# Memory.net
KiCad netlist of a schematic drawn in Altium Designer
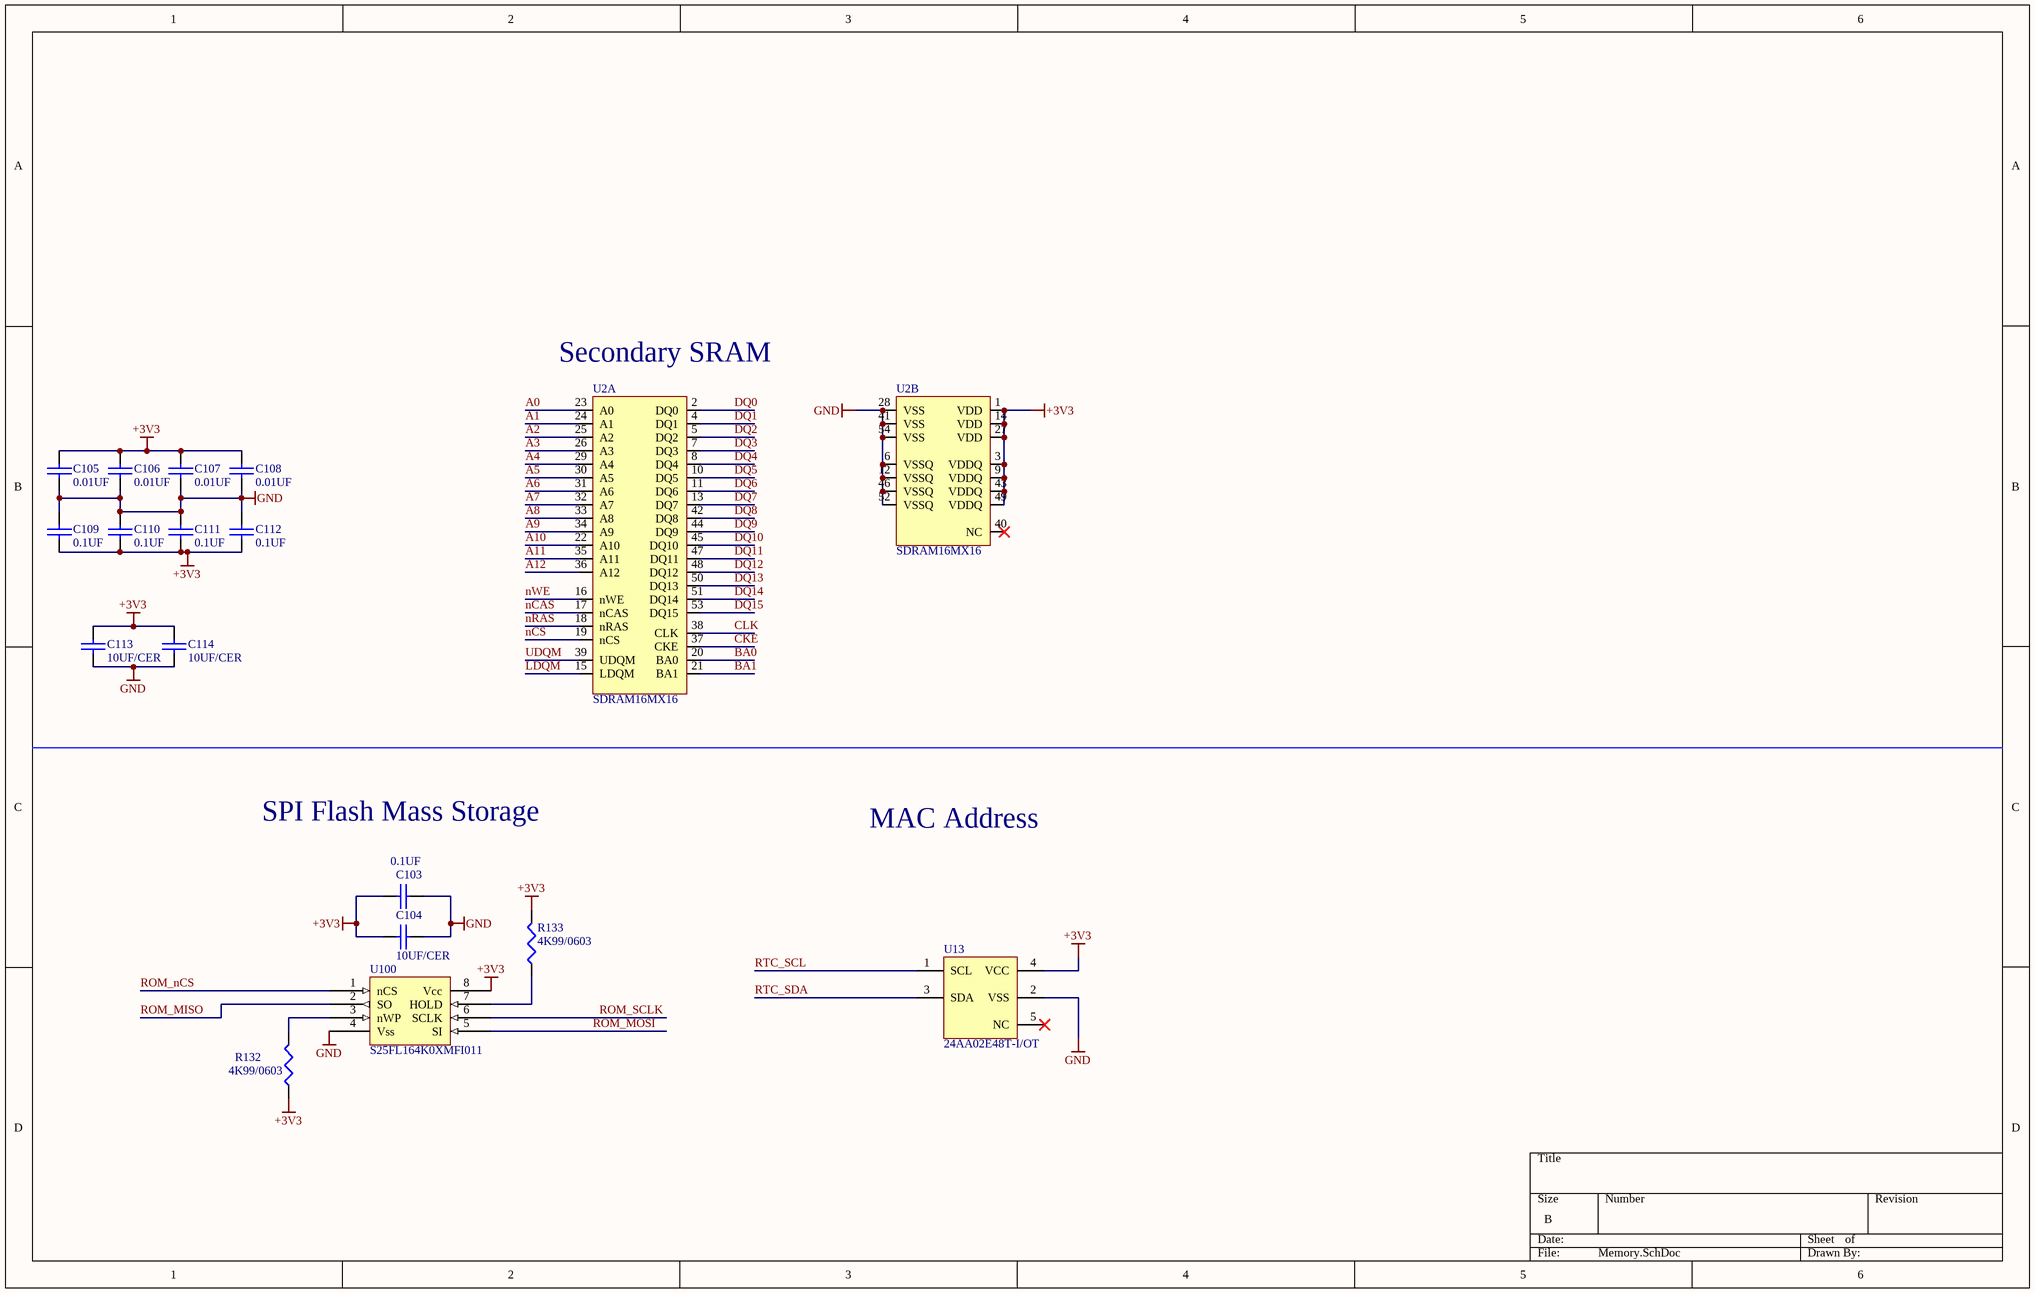
[diagram p0: Memory.SchDoc]

(export (version "E")
  (design (tool "Eeschema 10.0.6"))
  (components
    (comp (ref "C103")
      (value "0.1UF")
      (footprint "0603")
      (description "CAP .10UF 16V CERAMIC X7R 0603")
      (fields (field (name "MFG") "Kemet"))
      (libsource (lib "C64Interface") (part "0.1UF"))
    )
    (comp (ref "C104")
      (value "10UF/CER")
      (footprint "0805")
      (description "10µF ±10% 25V Ceramic Capacitor X7S 0805")
      (libsource (lib "*") (part "10UF/CER"))
    )
    (comp (ref "C105")
      (value "0.01UF")
      (footprint "0603")
      (description "10000pF ±10% 10V Ceramic Capacitor X7R 0603 (1608 Metric)")
      (fields (field (name "MFG") "Kemet"))
      (libsource (lib "C64Interface") (part "0.01UF"))
    )
    (comp (ref "C106")
      (value "0.01UF")
      (footprint "0603")
      (description "10000pF ±10% 10V Ceramic Capacitor X7R 0603 (1608 Metric)")
      (fields (field (name "MFG") "Kemet"))
      (libsource (lib "C64Interface") (part "0.01UF"))
    )
    (comp (ref "C107")
      (value "0.01UF")
      (footprint "0603")
      (description "10000pF ±10% 10V Ceramic Capacitor X7R 0603 (1608 Metric)")
      (fields (field (name "MFG") "Kemet"))
      (libsource (lib "C64Interface") (part "0.01UF"))
    )
    (comp (ref "C108")
      (value "0.01UF")
      (footprint "0603")
      (description "10000pF ±10% 10V Ceramic Capacitor X7R 0603 (1608 Metric)")
      (fields (field (name "MFG") "Kemet"))
      (libsource (lib "C64Interface") (part "0.01UF"))
    )
    (comp (ref "C109")
      (value "0.1UF")
      (footprint "0603")
      (description "CAP .10UF 16V CERAMIC X7R 0603")
      (fields (field (name "MFG") "Kemet"))
      (libsource (lib "C64Interface") (part "0.1UF"))
    )
    (comp (ref "C110")
      (value "0.1UF")
      (footprint "0603")
      (description "CAP .10UF 16V CERAMIC X7R 0603")
      (fields (field (name "MFG") "Kemet"))
      (libsource (lib "C64Interface") (part "0.1UF"))
    )
    (comp (ref "C111")
      (value "0.1UF")
      (footprint "0603")
      (description "CAP .10UF 16V CERAMIC X7R 0603")
      (fields (field (name "MFG") "Kemet"))
      (libsource (lib "C64Interface") (part "0.1UF"))
    )
    (comp (ref "C112")
      (value "0.1UF")
      (footprint "0603")
      (description "CAP .10UF 16V CERAMIC X7R 0603")
      (fields (field (name "MFG") "Kemet"))
      (libsource (lib "C64Interface") (part "0.1UF"))
    )
    (comp (ref "C113")
      (value "10UF/CER")
      (footprint "0805")
      (description "10µF ±10% 25V Ceramic Capacitor X7S 0805")
      (libsource (lib "C64Interface") (part "10UF/CER"))
    )
    (comp (ref "C114")
      (value "10UF/CER")
      (footprint "0805")
      (description "10µF ±10% 25V Ceramic Capacitor X7S 0805")
      (libsource (lib "C64Interface") (part "10UF/CER"))
    )
    (comp (ref "R132")
      (value "4K99/0603")
      (footprint "0603")
      (description "RES 4.99K OHM 1/10W 1% 0603 SMD")
      (fields (field (name "MFG") "Dale/Vishay"))
      (libsource (lib "C64Interface") (part "4K99/0603"))
    )
    (comp (ref "R133")
      (value "4K99/0603")
      (footprint "0603")
      (description "RES 4.99K OHM 1/10W 1% 0603 SMD")
      (fields (field (name "MFG") "Dale/Vishay"))
      (libsource (lib "C64Interface") (part "4K99/0603"))
    )
    (comp (ref "U2")
      (value "SDRAM16MX16")
      (footprint "SOP54")
      (description "SDRAM Memory IC 256Mb (16M x 16) Parallel 166MHz 5ns 54-TSOP II")
      (fields (field (name "MFG") "Winbond"))
      (libsource (lib "C64Interface") (part "SDRAM16MX16"))
    )
    (comp (ref "U13")
      (value "24AA02E48T-I/OT")
      (footprint "SOT23-5")
      (description "IC EEPROM 2KBIT 400KHZ SOT23-5")
      (fields (field (name "MFG") "Microchip"))
      (libsource (lib "APN") (part "24AA02E48T-I/OT"))
    )
    (comp (ref "U100")
      (value "S25FL164K0XMFI011")
      (footprint "SOC008")
      (description "IC FLASH 64MBIT 108MHZ 8SOIC")
      (libsource (lib "C64Interface") (part "S25FL164K0XMFI011"))
    )
  )
  (nets
    (net (code "1") (name "+3V3") (class "Default")
      (node (ref "C103") (pin "1") (pintype "passive"))
      (node (ref "C104") (pin "1") (pintype "passive"))
      (node (ref "C105") (pin "1") (pintype "passive"))
      (node (ref "C106") (pin "1") (pintype "passive"))
      (node (ref "C107") (pin "1") (pintype "passive"))
      (node (ref "C108") (pin "1") (pintype "passive"))
      (node (ref "C109") (pin "2") (pintype "passive"))
      (node (ref "C110") (pin "2") (pintype "passive"))
      (node (ref "C111") (pin "2") (pintype "passive"))
      (node (ref "C112") (pin "2") (pintype "passive"))
      (node (ref "C113") (pin "2") (pintype "passive"))
      (node (ref "C114") (pin "2") (pintype "passive"))
      (node (ref "R132") (pin "1") (pintype "passive"))
      (node (ref "R133") (pin "2") (pintype "passive"))
      (node (ref "U100") (pin "8") (pinfunction "Vcc_8") (pintype "power_in"))
      (node (ref "U13") (pin "4") (pinfunction "VCC_4") (pintype "power_in"))
      (node (ref "U2") (pin "1") (pinfunction "VDD_1") (pintype "passive"))
      (node (ref "U2") (pin "14") (pinfunction "VDD_14") (pintype "passive"))
      (node (ref "U2") (pin "27") (pinfunction "VDD_27") (pintype "passive"))
      (node (ref "U2") (pin "3") (pinfunction "VDDQ_3") (pintype "passive"))
      (node (ref "U2") (pin "43") (pinfunction "VDDQ_43") (pintype "passive"))
      (node (ref "U2") (pin "49") (pinfunction "VDDQ_49") (pintype "passive"))
      (node (ref "U2") (pin "9") (pinfunction "VDDQ_9") (pintype "passive"))
    )
    (net (code "2") (name "/A0") (class "Default")
      (node (ref "U2") (pin "23") (pinfunction "A0_23") (pintype "passive"))
    )
    (net (code "3") (name "/A1") (class "Default")
      (node (ref "U2") (pin "24") (pinfunction "A1_24") (pintype "passive"))
    )
    (net (code "4") (name "/A2") (class "Default")
      (node (ref "U2") (pin "25") (pinfunction "A2_25") (pintype "passive"))
    )
    (net (code "5") (name "/A3") (class "Default")
      (node (ref "U2") (pin "26") (pinfunction "A3_26") (pintype "passive"))
    )
    (net (code "6") (name "/A4") (class "Default")
      (node (ref "U2") (pin "29") (pinfunction "A4_29") (pintype "passive"))
    )
    (net (code "7") (name "/A5") (class "Default")
      (node (ref "U2") (pin "30") (pinfunction "A5_30") (pintype "passive"))
    )
    (net (code "8") (name "/A6") (class "Default")
      (node (ref "U2") (pin "31") (pinfunction "A6_31") (pintype "passive"))
    )
    (net (code "9") (name "/A7") (class "Default")
      (node (ref "U2") (pin "32") (pinfunction "A7_32") (pintype "passive"))
    )
    (net (code "10") (name "/A8") (class "Default")
      (node (ref "U2") (pin "33") (pinfunction "A8_33") (pintype "passive"))
    )
    (net (code "11") (name "/A9") (class "Default")
      (node (ref "U2") (pin "34") (pinfunction "A9_34") (pintype "passive"))
    )
    (net (code "12") (name "/A10") (class "Default")
      (node (ref "U2") (pin "22") (pinfunction "A10_22") (pintype "passive"))
    )
    (net (code "13") (name "/A11") (class "Default")
      (node (ref "U2") (pin "35") (pinfunction "A11_35") (pintype "passive"))
    )
    (net (code "14") (name "/A12") (class "Default")
      (node (ref "U2") (pin "36") (pinfunction "A12_36") (pintype "passive"))
    )
    (net (code "15") (name "/BA0") (class "Default")
      (node (ref "U2") (pin "20") (pinfunction "BA0_20") (pintype "passive"))
    )
    (net (code "16") (name "/BA1") (class "Default")
      (node (ref "U2") (pin "21") (pinfunction "BA1_21") (pintype "passive"))
    )
    (net (code "17") (name "/CKE") (class "Default")
      (node (ref "U2") (pin "37") (pinfunction "CKE_37") (pintype "passive"))
    )
    (net (code "18") (name "/CLK") (class "Default")
      (node (ref "U2") (pin "38") (pinfunction "CLK_38") (pintype "passive"))
    )
    (net (code "19") (name "/DQ0") (class "Default")
      (node (ref "U2") (pin "2") (pinfunction "DQ0_2") (pintype "passive"))
    )
    (net (code "20") (name "/DQ1") (class "Default")
      (node (ref "U2") (pin "4") (pinfunction "DQ1_4") (pintype "passive"))
    )
    (net (code "21") (name "/DQ2") (class "Default")
      (node (ref "U2") (pin "5") (pinfunction "DQ2_5") (pintype "passive"))
    )
    (net (code "22") (name "/DQ3") (class "Default")
      (node (ref "U2") (pin "7") (pinfunction "DQ3_7") (pintype "passive"))
    )
    (net (code "23") (name "/DQ4") (class "Default")
      (node (ref "U2") (pin "8") (pinfunction "DQ4_8") (pintype "passive"))
    )
    (net (code "24") (name "/DQ5") (class "Default")
      (node (ref "U2") (pin "10") (pinfunction "DQ5_10") (pintype "passive"))
    )
    (net (code "25") (name "/DQ6") (class "Default")
      (node (ref "U2") (pin "11") (pinfunction "DQ6_11") (pintype "passive"))
    )
    (net (code "26") (name "/DQ7") (class "Default")
      (node (ref "U2") (pin "13") (pinfunction "DQ7_13") (pintype "passive"))
    )
    (net (code "27") (name "/DQ8") (class "Default")
      (node (ref "U2") (pin "42") (pinfunction "DQ8_42") (pintype "passive"))
    )
    (net (code "28") (name "/DQ9") (class "Default")
      (node (ref "U2") (pin "44") (pinfunction "DQ9_44") (pintype "passive"))
    )
    (net (code "29") (name "/DQ10") (class "Default")
      (node (ref "U2") (pin "45") (pinfunction "DQ10_45") (pintype "passive"))
    )
    (net (code "30") (name "/DQ11") (class "Default")
      (node (ref "U2") (pin "47") (pinfunction "DQ11_47") (pintype "passive"))
    )
    (net (code "31") (name "/DQ12") (class "Default")
      (node (ref "U2") (pin "48") (pinfunction "DQ12_48") (pintype "passive"))
    )
    (net (code "32") (name "/DQ13") (class "Default")
      (node (ref "U2") (pin "50") (pinfunction "DQ13_50") (pintype "passive"))
    )
    (net (code "33") (name "/DQ14") (class "Default")
      (node (ref "U2") (pin "51") (pinfunction "DQ14_51") (pintype "passive"))
    )
    (net (code "34") (name "/DQ15") (class "Default")
      (node (ref "U2") (pin "53") (pinfunction "DQ15_53") (pintype "passive"))
    )
    (net (code "35") (name "/LDQM") (class "Default")
      (node (ref "U2") (pin "15") (pinfunction "LDQM_15") (pintype "passive"))
    )
    (net (code "36") (name "/ROM_MISO") (class "Default")
      (node (ref "U100") (pin "2") (pinfunction "SO_2") (pintype "output"))
    )
    (net (code "37") (name "/ROM_MOSI") (class "Default")
      (node (ref "U100") (pin "5") (pinfunction "SI_5") (pintype "input"))
    )
    (net (code "38") (name "/ROM_SCLK") (class "Default")
      (node (ref "U100") (pin "6") (pinfunction "SCLK_6") (pintype "input"))
    )
    (net (code "39") (name "/ROM_nCS") (class "Default")
      (node (ref "U100") (pin "1") (pinfunction "nCS_1") (pintype "input"))
    )
    (net (code "40") (name "/RTC_SCL") (class "Default")
      (node (ref "U13") (pin "1") (pinfunction "SCL_1") (pintype "power_in"))
    )
    (net (code "41") (name "/RTC_SDA") (class "Default")
      (node (ref "U13") (pin "3") (pinfunction "SDA_3") (pintype "power_in"))
    )
    (net (code "42") (name "/UDQM") (class "Default")
      (node (ref "U2") (pin "39") (pinfunction "UDQM_39") (pintype "passive"))
    )
    (net (code "43") (name "/nCAS") (class "Default")
      (node (ref "U2") (pin "17") (pinfunction "nCAS_17") (pintype "passive"))
    )
    (net (code "44") (name "/nCS") (class "Default")
      (node (ref "U2") (pin "19") (pinfunction "nCS_19") (pintype "passive"))
    )
    (net (code "45") (name "/nRAS") (class "Default")
      (node (ref "U2") (pin "18") (pinfunction "nRAS_18") (pintype "passive"))
    )
    (net (code "46") (name "/nWE") (class "Default")
      (node (ref "U2") (pin "16") (pinfunction "nWE_16") (pintype "passive"))
    )
    (net (code "47") (name "GND") (class "Default")
      (node (ref "C103") (pin "2") (pintype "passive"))
      (node (ref "C104") (pin "2") (pintype "passive"))
      (node (ref "C105") (pin "2") (pintype "passive"))
      (node (ref "C106") (pin "2") (pintype "passive"))
      (node (ref "C107") (pin "2") (pintype "passive"))
      (node (ref "C108") (pin "2") (pintype "passive"))
      (node (ref "C109") (pin "1") (pintype "passive"))
      (node (ref "C110") (pin "1") (pintype "passive"))
      (node (ref "C111") (pin "1") (pintype "passive"))
      (node (ref "C112") (pin "1") (pintype "passive"))
      (node (ref "C113") (pin "1") (pintype "passive"))
      (node (ref "C114") (pin "1") (pintype "passive"))
      (node (ref "U100") (pin "4") (pinfunction "Vss_4") (pintype "power_in"))
      (node (ref "U13") (pin "2") (pinfunction "VSS_2") (pintype "power_in"))
      (node (ref "U2") (pin "12") (pinfunction "VSSQ_12") (pintype "passive"))
      (node (ref "U2") (pin "28") (pinfunction "VSS_28") (pintype "passive"))
      (node (ref "U2") (pin "41") (pinfunction "VSS_41") (pintype "passive"))
      (node (ref "U2") (pin "46") (pinfunction "VSSQ_46") (pintype "passive"))
      (node (ref "U2") (pin "52") (pinfunction "VSSQ_52") (pintype "passive"))
      (node (ref "U2") (pin "54") (pinfunction "VSS_54") (pintype "passive"))
      (node (ref "U2") (pin "6") (pinfunction "VSSQ_6") (pintype "passive"))
    )
    (net (code "48") (name "Net-(U100-HOLD)") (class "Default")
      (node (ref "R133") (pin "1") (pintype "passive"))
      (node (ref "U100") (pin "7") (pinfunction "HOLD_7") (pintype "input"))
    )
    (net (code "49") (name "Net-(U100-nWP)") (class "Default")
      (node (ref "R132") (pin "2") (pintype "passive"))
      (node (ref "U100") (pin "3") (pinfunction "nWP_3") (pintype "input"))
    )
    (net (code "50") (name "unconnected-(U2B-NC-Pad40)") (class "Default")
      (node (ref "U2") (pin "40") (pinfunction "NC_40") (pintype "passive+no_connect"))
    )
    (net (code "51") (name "unconnected-(U13-NC-Pad5)") (class "Default")
      (node (ref "U13") (pin "5") (pinfunction "NC_5") (pintype "power_in+no_connect"))
    )
  )
)
